# TESTER_SENSOR_HAL_AT24xx.net
KiCad netlist of a schematic drawn in Altium Designer
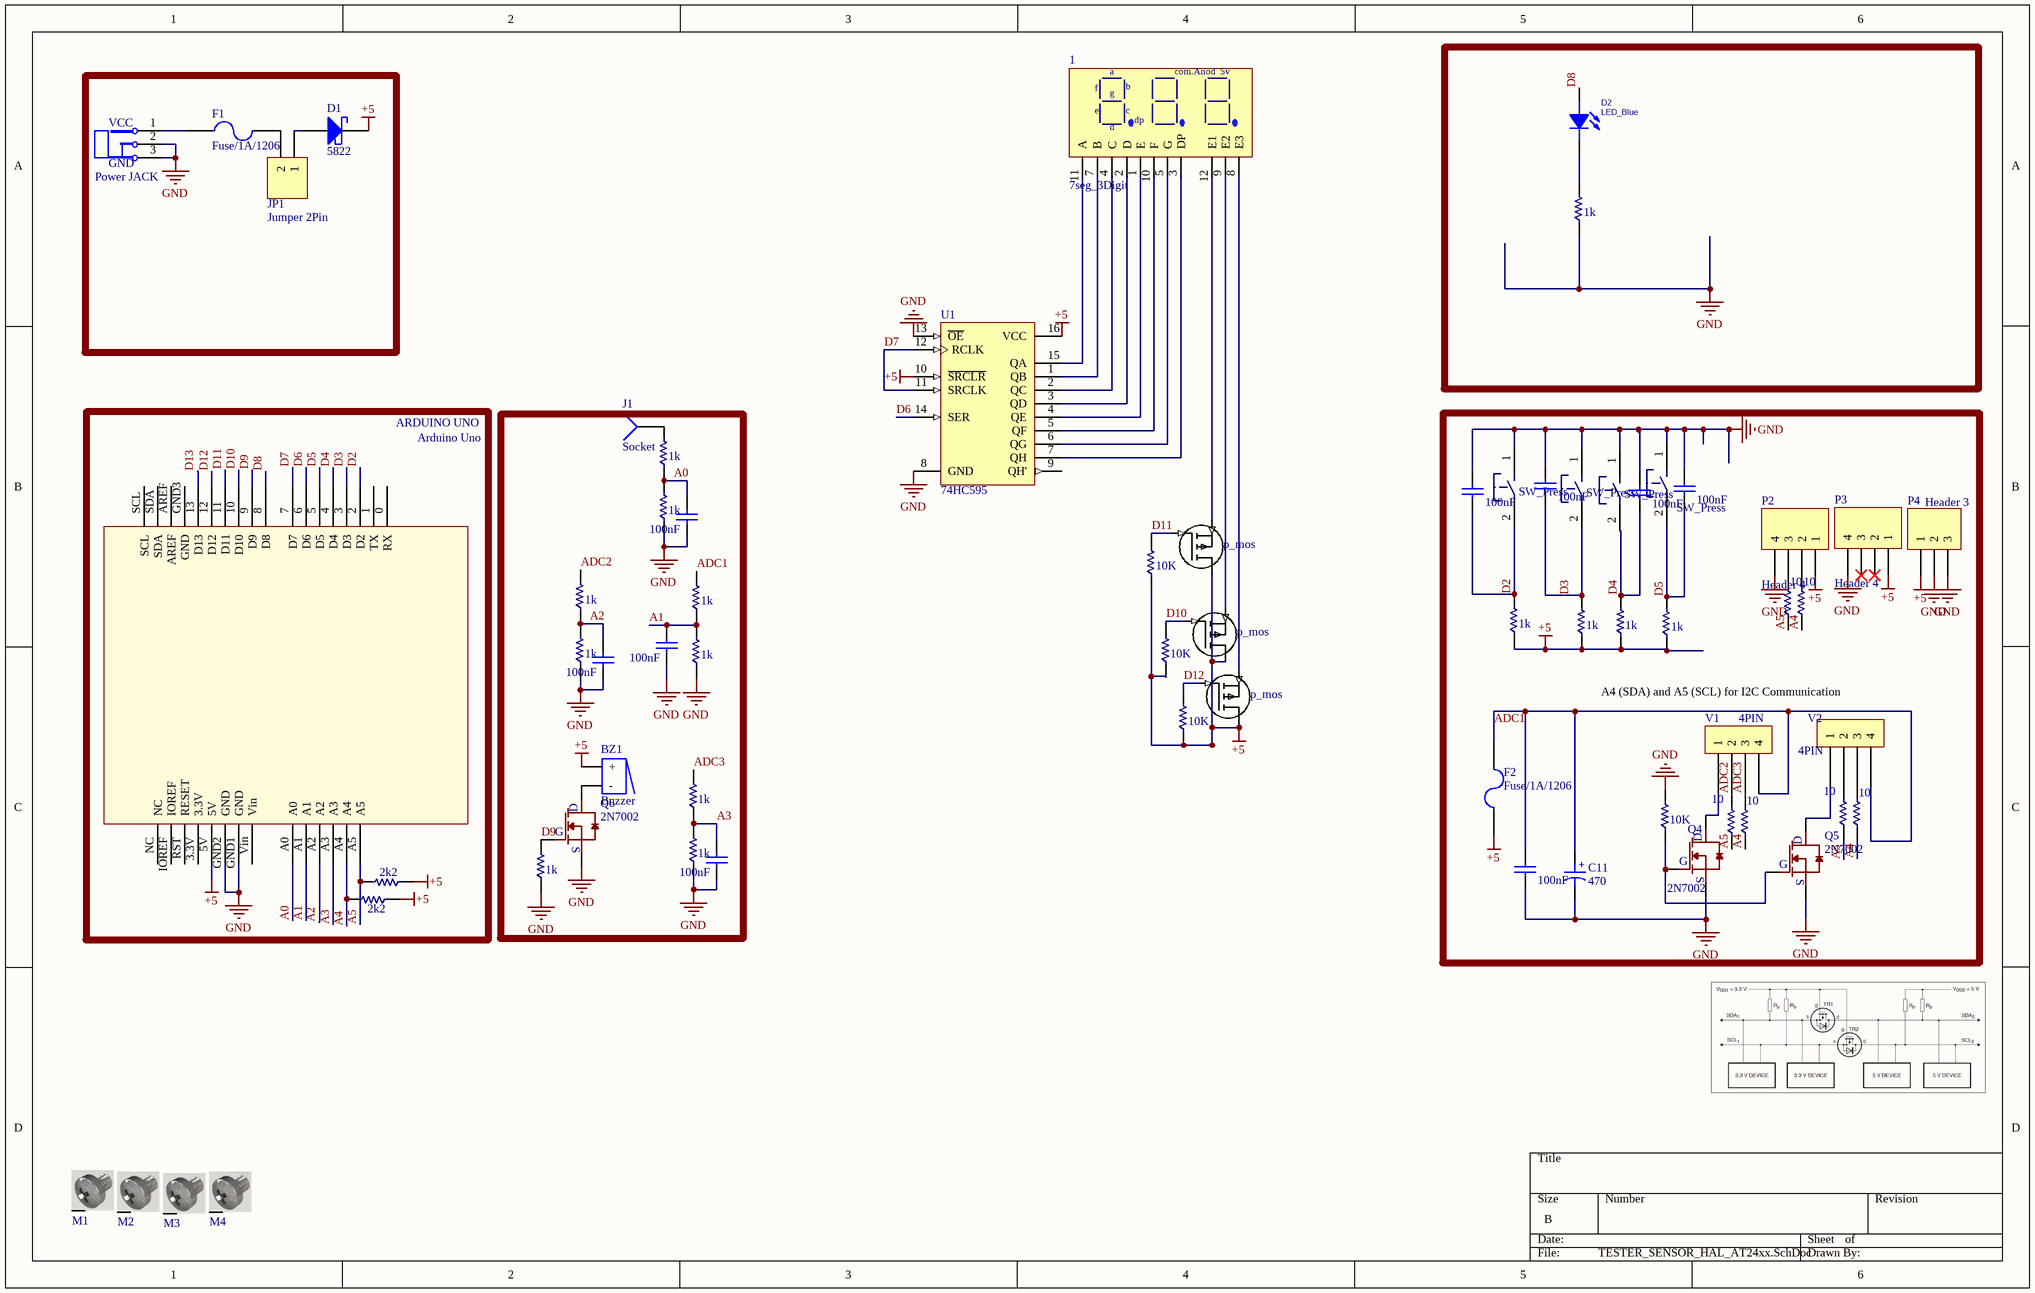
[diagram p0: TESTER_SENSOR_HAL_AT24xx.SchDoc]

(export (version "E")
  (design (tool "Eeschema 10.0.6"))
  (components
    (comp (ref "1")
      (value "7seg_3Digit")
      (footprint "7Segment")
      (description "7Segment-3 Digit- Anode Common")
      (fields (field (name "PART") "7Segment-3Digit"))
      (libsource (lib "R_C_D_T") (part "7Segment-3Digit"))
    )
    (comp (ref "Arduino Uno")
      (value "ARDUINO UNO")
      (footprint "ARDUINO UNO")
      (libsource (lib "Arduino") (part "ARDUINO UNO"))
    )
    (comp (ref "BZ1")
      (value "Buzzer")
      (footprint "Buzzer 3M")
      (fields (field (name "PART") "BUZZER 5V") (field (name "POWER") "CHINA"))
      (libsource (lib "NKH_Contacts") (part "Buzzer_small"))
    )
    (comp (ref "C2")
      (value "100nF")
      (footprint "CAP1206")
      (description "cap_no_polar_seramic_multilayer")
      (fields (field (name "PART") "Cap-smd-1206-100nf"))
      (libsource (lib "R_C_D_T") (part "cap_no_polar_sig"))
    )
    (comp (ref "C3")
      (value "100nF")
      (footprint "CAP1206")
      (description "cap_no_polar_seramic_multilayer")
      (fields (field (name "PART") "Cap-smd-1206-100nf"))
      (libsource (lib "R_C_D_T") (part "cap_no_polar_sig"))
    )
    (comp (ref "C4")
      (value "100nF")
      (footprint "CAP1206")
      (description "cap_no_polar_seramic_multilayer")
      (fields (field (name "PART") "Cap-smd-1206-100nf"))
      (libsource (lib "R_C_D_T") (part "cap_no_polar_sig"))
    )
    (comp (ref "C5")
      (value "100nF")
      (footprint "CAP1206")
      (description "cap_no_polar_seramic_multilayer")
      (fields (field (name "PART") "Cap-smd-1206-100nf"))
      (libsource (lib "R_C_D_T") (part "cap_no_polar_sig"))
    )
    (comp (ref "C6")
      (value "100nF")
      (footprint "CAP1206")
      (description "cap_no_polar_seramic_multilayer")
      (fields (field (name "PART") "Cap-smd-1206-100nf"))
      (libsource (lib "R_C_D_T") (part "cap_no_polar_sig"))
    )
    (comp (ref "C7")
      (value "100nF")
      (footprint "CAP1206")
      (description "cap_no_polar_seramic_multilayer")
      (fields (field (name "PART") "Cap-smd-1206-100nf"))
      (libsource (lib "R_C_D_T") (part "cap_no_polar_sig"))
    )
    (comp (ref "C8")
      (value "100nF")
      (footprint "CAP1206")
      (description "cap_no_polar_seramic_multilayer")
      (fields (field (name "PART") "Cap-smd-1206-100nf"))
      (libsource (lib "R_C_D_T") (part "cap_no_polar_sig"))
    )
    (comp (ref "C9")
      (value "100nF")
      (footprint "CAP1206")
      (description "cap_no_polar_seramic_multilayer")
      (fields (field (name "PART") "Cap-smd-1206-100nf"))
      (libsource (lib "R_C_D_T") (part "cap_no_polar_sig"))
    )
    (comp (ref "C10")
      (value "100nF")
      (footprint "CAP1206")
      (description "cap_no_polar_seramic_multilayer")
      (fields (field (name "PART") "Cap-smd-1206-100nf"))
      (libsource (lib "R_C_D_T") (part "cap_no_polar_sig"))
    )
    (comp (ref "C11")
      (value "470")
      (footprint "CAP_POLAR_8X11.5")
      (description "Cap electrolitic radial")
      (fields (field (name "PART") "Cap-pol-dip-470uf_16V") (field (name "DESIGNER") "rashid_behdarvand"))
      (libsource (lib "R_C_D_T") (part "Cap_polar"))
    )
    (comp (ref "D1")
      (value "5822")
      (footprint "SMA_Diode")
      (fields (field (name "PART") "Diode-shotkey-SMB5822"))
      (libsource (lib "R_C_D_T") (part "Diode_1n5817"))
    )
    (comp (ref "D2")
      (value "LED_Blue")
      (footprint "LED-3mm")
      (description "LED LIGHTING 5mm Blue")
      (fields (field (name "PART") "LED3MM_RED") (field (name "DESIGNER") "Abbas Basereh"))
      (libsource (lib "R_C_D_T") (part "LED5MM_Blue"))
    )
    (comp (ref "F1")
      (value "Fuse")
      (footprint "Fuse 1206 smd")
      (fields (field (name "ALTIUM_UNNAMED_1") "Fuse/1A/1206") (field (name "PART") "Fuse 1206 smd"))
      (libsource (lib "R_C_D_T") (part "Fuse SMT"))
    )
    (comp (ref "F2")
      (value "Fuse")
      (footprint "Fuse 1206 smd")
      (fields (field (name "ALTIUM_UNNAMED_1") "Fuse/1A/1206") (field (name "PART") "Fuse 1206 smd"))
      (libsource (lib "R_C_D_T") (part "Fuse SMT"))
    )
    (comp (ref "J1")
      (value "Socket")
      (footprint "PIN1")
      (fields (field (name "PUBLISHER") "Altium Limited"))
      (libsource (lib "NKH_Contacts") (part "Socket"))
    )
    (comp (ref "JP1")
      (value "Jumper 2Pin")
      (footprint "Jumper Small - 2.54 - RED")
      (description "Jumper, 2-Pin")
      (fields (field (name "DESIGNER") "Abbas Basereh"))
      (libsource (lib "NKH_Contacts") (part "Jumper 2Pin"))
    )
    (comp (ref "M1")
      (value "Screw")
      (footprint "Board Screw_No Silk")
      (description "Board Screw With Spacer")
      (libsource (lib "QUECTEL_MC60") (part "Board Screw"))
    )
    (comp (ref "M2")
      (value "Screw")
      (footprint "Board Screw_No Silk")
      (description "Board Screw With Spacer")
      (libsource (lib "QUECTEL_MC60") (part "Board Screw"))
    )
    (comp (ref "M3")
      (value "Screw")
      (footprint "Board Screw_No Silk")
      (description "Board Screw With Spacer")
      (libsource (lib "QUECTEL_MC60") (part "Board Screw"))
    )
    (comp (ref "M4")
      (value "Screw")
      (footprint "Board Screw_No Silk")
      (description "Board Screw With Spacer")
      (libsource (lib "QUECTEL_MC60") (part "Board Screw"))
    )
    (comp (ref "P1")
      (value "Power JACK")
      (footprint "power jack")
      (fields (field (name "PART") "dc jack adaptor"))
      (libsource (lib "NKH_Contacts") (part "PHONE JACK"))
    )
    (comp (ref "P2")
      (value "Header 4")
      (footprint "HDR1X4")
      (description "Header, 4-Pin")
      (fields (field (name "PUBLISHER") "Altium Limited"))
      (libsource (lib "Miscellaneous Connectors") (part "Header 4"))
    )
    (comp (ref "P3")
      (value "Header 4")
      (footprint "HDR1X4")
      (description "Header, 4-Pin")
      (fields (field (name "PUBLISHER") "Altium Limited"))
      (libsource (lib "Miscellaneous Connectors") (part "Header 4"))
    )
    (comp (ref "P4")
      (value "Header 3")
      (footprint "HDR1X3")
      (description "Header, 3-Pin")
      (fields (field (name "PUBLISHER") "Altium Limited"))
      (libsource (lib "Miscellaneous Connectors") (part "Header 3"))
    )
    (comp (ref "Q1")
      (value "p_mos")
      (footprint "SOT23_BEC_M")
      (description "P CHANNEL MOSFET")
      (fields (field (name "MANUFACTURER") "Diodes Inc") (field (name "PART") "Mosfet-p-channel-AO3401"))
      (libsource (lib "R_C_D_T") (part "p_mos"))
    )
    (comp (ref "Q2")
      (value "p_mos")
      (footprint "SOT23_BEC_M")
      (description "P CHANNEL MOSFET")
      (fields (field (name "MANUFACTURER") "Diodes Inc") (field (name "PART") "Mosfet-p-channel-AO3401"))
      (libsource (lib "R_C_D_T") (part "p_mos"))
    )
    (comp (ref "Q3")
      (value "p_mos")
      (footprint "SOT23_BEC_M")
      (description "P CHANNEL MOSFET")
      (fields (field (name "MANUFACTURER") "Diodes Inc") (field (name "PART") "Mosfet-p-channel-AO3401"))
      (libsource (lib "R_C_D_T") (part "p_mos"))
    )
    (comp (ref "Q4")
      (value "2N7002")
      (footprint "SOT23_BEC_M")
      (fields (field (name "PART") "Mosfet-n-channel-2n7002"))
      (libsource (lib "R_C_D_T") (part "2N7002"))
    )
    (comp (ref "Q5")
      (value "2N7002")
      (footprint "SOT23_BEC_M")
      (fields (field (name "PART") "Mosfet-n-channel-2n7002"))
      (libsource (lib "R_C_D_T") (part "2N7002"))
    )
    (comp (ref "Q6")
      (value "2N7002")
      (footprint "SOT23_BEC_M")
      (fields (field (name "PART") "Mosfet-n-channel-2n7002"))
      (libsource (lib "R_C_D_T") (part "2N7002"))
    )
    (comp (ref "R1")
      (value "1k")
      (footprint "RES1206")
      (fields (field (name "PART") "resistor-smd-1206-1k") (field (name "DESIGNER") "rashid_behdarvand"))
      (libsource (lib "R_C_D_T") (part "resistor"))
    )
    (comp (ref "R2")
      (value "1k")
      (footprint "RES1206")
      (fields (field (name "PART") "resistor-smd-1206-1k") (field (name "DESIGNER") "rashid_behdarvand"))
      (libsource (lib "R_C_D_T") (part "resistor"))
    )
    (comp (ref "R3")
      (value "1k")
      (footprint "RES1206")
      (fields (field (name "PART") "resistor-smd-1206-1k") (field (name "DESIGNER") "rashid_behdarvand"))
      (libsource (lib "R_C_D_T") (part "resistor"))
    )
    (comp (ref "R4")
      (value "1k")
      (footprint "RES1206")
      (fields (field (name "PART") "resistor-smd-1206-1k") (field (name "DESIGNER") "rashid_behdarvand"))
      (libsource (lib "R_C_D_T") (part "resistor"))
    )
    (comp (ref "R5")
      (value "10")
      (footprint "RES1206")
      (fields (field (name "PART") "resistor-smd-1206-1k") (field (name "DESIGNER") "rashid_behdarvand"))
      (libsource (lib "R_C_D_T") (part "resistor"))
    )
    (comp (ref "R6")
      (value "10")
      (footprint "RES1206")
      (fields (field (name "PART") "resistor-smd-1206-1k") (field (name "DESIGNER") "rashid_behdarvand"))
      (libsource (lib "R_C_D_T") (part "resistor"))
    )
    (comp (ref "R7")
      (value "1k")
      (footprint "RES1206")
      (fields (field (name "PART") "resistor-smd-1206-1k") (field (name "DESIGNER") "rashid_behdarvand"))
      (libsource (lib "R_C_D_T") (part "resistor"))
    )
    (comp (ref "R8")
      (value "1k")
      (footprint "RES1206")
      (fields (field (name "PART") "resistor-smd-1206-1k") (field (name "DESIGNER") "rashid_behdarvand"))
      (libsource (lib "R_C_D_T") (part "resistor"))
    )
    (comp (ref "R9")
      (value "1k")
      (footprint "RES1206")
      (fields (field (name "PART") "resistor-smd-1206-1k") (field (name "DESIGNER") "rashid_behdarvand"))
      (libsource (lib "R_C_D_T") (part "resistor"))
    )
    (comp (ref "R10")
      (value "10")
      (footprint "RES1206")
      (fields (field (name "PART") "resistor-smd-1206-1k") (field (name "DESIGNER") "rashid_behdarvand"))
      (libsource (lib "R_C_D_T") (part "resistor"))
    )
    (comp (ref "R11")
      (value "10")
      (footprint "RES1206")
      (fields (field (name "PART") "resistor-smd-1206-1k") (field (name "DESIGNER") "rashid_behdarvand"))
      (libsource (lib "R_C_D_T") (part "resistor"))
    )
    (comp (ref "R12")
      (value "10")
      (footprint "RES1206")
      (fields (field (name "PART") "resistor-smd-1206-1k") (field (name "DESIGNER") "rashid_behdarvand"))
      (libsource (lib "R_C_D_T") (part "resistor"))
    )
    (comp (ref "R13")
      (value "10")
      (footprint "RES1206")
      (fields (field (name "PART") "resistor-smd-1206-1k") (field (name "DESIGNER") "rashid_behdarvand"))
      (libsource (lib "R_C_D_T") (part "resistor"))
    )
    (comp (ref "R14")
      (value "1k")
      (footprint "RES1206")
      (fields (field (name "PART") "resistor-smd-1206-1k") (field (name "DESIGNER") "rashid_behdarvand"))
      (libsource (lib "R_C_D_T") (part "resistor"))
    )
    (comp (ref "R15")
      (value "1k")
      (footprint "RES1206")
      (fields (field (name "PART") "resistor-smd-1206-1k") (field (name "DESIGNER") "rashid_behdarvand"))
      (libsource (lib "R_C_D_T") (part "resistor"))
    )
    (comp (ref "R16")
      (value "2k2")
      (footprint "RES1206")
      (fields (field (name "PART") "resistor-smd-1206-1k") (field (name "DESIGNER") "rashid_behdarvand"))
      (libsource (lib "R_C_D_T") (part "resistor"))
    )
    (comp (ref "R17")
      (value "2k2")
      (footprint "RES1206")
      (fields (field (name "PART") "resistor-smd-1206-1k") (field (name "DESIGNER") "rashid_behdarvand"))
      (libsource (lib "R_C_D_T") (part "resistor"))
    )
    (comp (ref "R18")
      (value "10K")
      (footprint "RES1206")
      (fields (field (name "PART") "resistor-smd-1206-1k") (field (name "DESIGNER") "rashid_behdarvand"))
      (libsource (lib "R_C_D_T") (part "resistor"))
    )
    (comp (ref "R19")
      (value "10K")
      (footprint "RES1206")
      (fields (field (name "PART") "resistor-smd-1206-1k") (field (name "DESIGNER") "rashid_behdarvand"))
      (libsource (lib "R_C_D_T") (part "resistor"))
    )
    (comp (ref "R20")
      (value "10K")
      (footprint "RES1206")
      (fields (field (name "PART") "resistor-smd-1206-1k") (field (name "DESIGNER") "rashid_behdarvand"))
      (libsource (lib "R_C_D_T") (part "resistor"))
    )
    (comp (ref "R21")
      (value "10K")
      (footprint "RES1206")
      (fields (field (name "PART") "resistor-smd-1206-1k") (field (name "DESIGNER") "rashid_behdarvand"))
      (libsource (lib "R_C_D_T") (part "resistor"))
    )
    (comp (ref "res1")
      (value "1k")
      (footprint "RES1206")
      (fields (field (name "PART") "resistor-smd-1206-1k") (field (name "DESIGNER") "rashid_behdarvand"))
      (libsource (lib "R_C_D_T") (part "resistor"))
    )
    (comp (ref "res5")
      (value "1k")
      (footprint "RES1206")
      (fields (field (name "PART") "resistor-smd-1206-1k") (field (name "DESIGNER") "rashid_behdarvand"))
      (libsource (lib "R_C_D_T") (part "resistor"))
    )
    (comp (ref "res6")
      (value "1k")
      (footprint "RES1206")
      (fields (field (name "PART") "resistor-smd-1206-1k") (field (name "DESIGNER") "rashid_behdarvand"))
      (libsource (lib "R_C_D_T") (part "resistor"))
    )
    (comp (ref "res7")
      (value "1k")
      (footprint "RES1206")
      (fields (field (name "PART") "resistor-smd-1206-1k") (field (name "DESIGNER") "rashid_behdarvand"))
      (libsource (lib "R_C_D_T") (part "resistor"))
    )
    (comp (ref "res8")
      (value "1k")
      (footprint "RES1206")
      (fields (field (name "PART") "resistor-smd-1206-1k") (field (name "DESIGNER") "rashid_behdarvand"))
      (libsource (lib "R_C_D_T") (part "resistor"))
    )
    (comp (ref "sw1")
      (value "SW_Press")
      (footprint "tact_kfc-12x12")
      (description "small tac switch")
      (fields (field (name "PART") "tac switch kfc-12x12x12"))
      (libsource (lib "NKH_Contacts") (part "Tac switch"))
    )
    (comp (ref "sw3")
      (value "SW_Press")
      (footprint "tact_kfc-12x12")
      (description "small tac switch")
      (fields (field (name "PART") "tac switch kfc-12x12x12"))
      (libsource (lib "NKH_Contacts") (part "Tac switch"))
    )
    (comp (ref "sw4")
      (value "SW_Press")
      (footprint "tact_kfc-12x12")
      (description "small tac switch")
      (fields (field (name "PART") "tac switch kfc-12x12x12"))
      (libsource (lib "NKH_Contacts") (part "Tac switch"))
    )
    (comp (ref "sw5")
      (value "SW_Press")
      (footprint "tact_kfc-12x12")
      (description "small tac switch")
      (fields (field (name "PART") "tac switch kfc-12x12x12"))
      (libsource (lib "NKH_Contacts") (part "Tac switch"))
    )
    (comp (ref "U1")
      (value "74HC595")
      (footprint "SO16_N")
      (description "8 Bit Shift Register with Output Latches (3 STATE)")
      (fields (field (name "PART") "74HC595 SMD") (field (name "PUBLISHER") "Altium Limited"))
      (libsource (lib "NKH_IC") (part "M74HC595M1R"))
    )
    (comp (ref "V1")
      (value "4PIN")
      (footprint "4PIN")
      (description "connector power 4pin stright lock")
      (fields (field (name "PART") "VH_ST_4pin"))
      (libsource (lib "NKH_Contacts") (part "VH_ST_4pin"))
    )
    (comp (ref "V2")
      (value "4PIN")
      (footprint "4PIN")
      (description "connector power 4pin stright lock")
      (fields (field (name "PART") "VH_ST_4pin"))
      (libsource (lib "NKH_Contacts") (part "VH_ST_4pin"))
    )
  )
  (nets
    (net (code "1") (name "+5") (class "Default")
      (node (ref "Arduino Uno") (pin "5V") (pinfunction "5V_5V") (pintype "passive"))
      (node (ref "BZ1") (pin "1") (pinfunction "+_1") (pintype "passive"))
      (node (ref "D1") (pin "2") (pinfunction "K_2") (pintype "passive"))
      (node (ref "F2") (pin "2") (pinfunction "2_2") (pintype "passive"))
      (node (ref "P2") (pin "1") (pinfunction "1_1") (pintype "passive"))
      (node (ref "P3") (pin "1") (pinfunction "1_1") (pintype "passive"))
      (node (ref "P4") (pin "1") (pinfunction "1_1") (pintype "passive"))
      (node (ref "Q1") (pin "3") (pintype "passive"))
      (node (ref "Q2") (pin "3") (pintype "passive"))
      (node (ref "Q3") (pin "3") (pintype "passive"))
      (node (ref "R16") (pin "1") (pinfunction "1_1") (pintype "passive"))
      (node (ref "R17") (pin "1") (pinfunction "1_1") (pintype "passive"))
      (node (ref "R18") (pin "1") (pinfunction "1_1") (pintype "passive"))
      (node (ref "R19") (pin "1") (pinfunction "1_1") (pintype "passive"))
      (node (ref "R20") (pin "1") (pinfunction "1_1") (pintype "passive"))
      (node (ref "U1") (pin "10") (pinfunction "~{SRCLR}_10") (pintype "input"))
      (node (ref "U1") (pin "16") (pinfunction "VCC_16") (pintype "power_in"))
      (node (ref "res5") (pin "1") (pinfunction "1_1") (pintype "passive"))
      (node (ref "res6") (pin "1") (pinfunction "1_1") (pintype "passive"))
      (node (ref "res7") (pin "1") (pinfunction "1_1") (pintype "passive"))
      (node (ref "res8") (pin "1") (pinfunction "1_1") (pintype "passive"))
    )
    (net (code "2") (name "/A0") (class "Default")
      (node (ref "Arduino Uno") (pin "A0") (pinfunction "A0_A0") (pintype "passive"))
      (node (ref "C6") (pin "2") (pinfunction "2_2") (pintype "passive"))
      (node (ref "R1") (pin "1") (pinfunction "1_1") (pintype "passive"))
      (node (ref "R2") (pin "2") (pinfunction "2_2") (pintype "passive"))
    )
    (net (code "3") (name "/A1") (class "Default")
      (node (ref "Arduino Uno") (pin "A1") (pinfunction "A1_A1") (pintype "passive"))
      (node (ref "C7") (pin "2") (pinfunction "2_2") (pintype "passive"))
      (node (ref "R4") (pin "1") (pinfunction "1_1") (pintype "passive"))
      (node (ref "R8") (pin "2") (pinfunction "2_2") (pintype "passive"))
    )
    (net (code "4") (name "/A2") (class "Default")
      (node (ref "Arduino Uno") (pin "A2") (pinfunction "A2_A2") (pintype "passive"))
      (node (ref "C8") (pin "2") (pinfunction "2_2") (pintype "passive"))
      (node (ref "R3") (pin "1") (pinfunction "1_1") (pintype "passive"))
      (node (ref "R7") (pin "2") (pinfunction "2_2") (pintype "passive"))
    )
    (net (code "5") (name "/A3") (class "Default")
      (node (ref "Arduino Uno") (pin "A3") (pinfunction "A3_A3") (pintype "passive"))
      (node (ref "C9") (pin "2") (pinfunction "2_2") (pintype "passive"))
      (node (ref "R14") (pin "2") (pinfunction "2_2") (pintype "passive"))
      (node (ref "R9") (pin "1") (pinfunction "1_1") (pintype "passive"))
    )
    (net (code "6") (name "/A4") (class "Default")
      (node (ref "Arduino Uno") (pin "A4") (pinfunction "A4_A4") (pintype "passive"))
      (node (ref "R11") (pin "1") (pinfunction "1_1") (pintype "passive"))
      (node (ref "R13") (pin "1") (pinfunction "1_1") (pintype "passive"))
      (node (ref "R17") (pin "2") (pinfunction "2_2") (pintype "passive"))
      (node (ref "R6") (pin "1") (pinfunction "1_1") (pintype "passive"))
    )
    (net (code "7") (name "/A5") (class "Default")
      (node (ref "Arduino Uno") (pin "A5") (pinfunction "A5_A5") (pintype "passive"))
      (node (ref "R10") (pin "1") (pinfunction "1_1") (pintype "passive"))
      (node (ref "R12") (pin "1") (pinfunction "1_1") (pintype "passive"))
      (node (ref "R16") (pin "2") (pinfunction "2_2") (pintype "passive"))
      (node (ref "R5") (pin "1") (pinfunction "1_1") (pintype "passive"))
    )
    (net (code "8") (name "/ADC1") (class "Default")
      (node (ref "C10") (pin "2") (pinfunction "2_2") (pintype "passive"))
      (node (ref "C11") (pin "1") (pinfunction "1_1") (pintype "passive"))
      (node (ref "F2") (pin "1") (pinfunction "1_1") (pintype "passive"))
      (node (ref "R4") (pin "2") (pinfunction "2_2") (pintype "passive"))
      (node (ref "V1") (pin "4") (pinfunction "4_4") (pintype "passive"))
      (node (ref "V2") (pin "4") (pinfunction "4_4") (pintype "passive"))
    )
    (net (code "9") (name "/ADC2") (class "Default")
      (node (ref "R12") (pin "2") (pinfunction "2_2") (pintype "passive"))
      (node (ref "R3") (pin "2") (pinfunction "2_2") (pintype "passive"))
      (node (ref "V1") (pin "2") (pinfunction "2_2") (pintype "passive"))
    )
    (net (code "10") (name "/ADC3") (class "Default")
      (node (ref "R13") (pin "2") (pinfunction "2_2") (pintype "passive"))
      (node (ref "R9") (pin "2") (pinfunction "2_2") (pintype "passive"))
      (node (ref "V1") (pin "3") (pinfunction "3_3") (pintype "passive"))
    )
    (net (code "11") (name "/D2") (class "Default")
      (node (ref "Arduino Uno") (pin "2") (pinfunction "D2_2") (pintype "passive"))
      (node (ref "C4") (pin "1") (pinfunction "1_1") (pintype "passive"))
      (node (ref "res5") (pin "2") (pinfunction "2_2") (pintype "passive"))
      (node (ref "sw3") (pin "2") (pinfunction "2_2") (pintype "passive"))
    )
    (net (code "12") (name "/D3") (class "Default")
      (node (ref "Arduino Uno") (pin "3") (pinfunction "D3_3") (pintype "passive"))
      (node (ref "C2") (pin "1") (pinfunction "1_1") (pintype "passive"))
      (node (ref "res6") (pin "2") (pinfunction "2_2") (pintype "passive"))
      (node (ref "sw5") (pin "2") (pinfunction "2_2") (pintype "passive"))
    )
    (net (code "13") (name "/D4") (class "Default")
      (node (ref "Arduino Uno") (pin "4") (pinfunction "D4_4") (pintype "passive"))
      (node (ref "C5") (pin "1") (pinfunction "1_1") (pintype "passive"))
      (node (ref "res7") (pin "2") (pinfunction "2_2") (pintype "passive"))
      (node (ref "sw4") (pin "2") (pinfunction "2_2") (pintype "passive"))
    )
    (net (code "14") (name "/D5") (class "Default")
      (node (ref "Arduino Uno") (pin "5") (pinfunction "D5_5") (pintype "passive"))
      (node (ref "C3") (pin "1") (pinfunction "1_1") (pintype "passive"))
      (node (ref "res8") (pin "2") (pinfunction "2_2") (pintype "passive"))
      (node (ref "sw1") (pin "2") (pinfunction "2_2") (pintype "passive"))
    )
    (net (code "15") (name "/D6") (class "Default")
      (node (ref "Arduino Uno") (pin "6") (pinfunction "D6_6") (pintype "passive"))
      (node (ref "U1") (pin "14") (pinfunction "SER_14") (pintype "input"))
    )
    (net (code "16") (name "/D7") (class "Default")
      (node (ref "Arduino Uno") (pin "7") (pinfunction "D7_7") (pintype "passive"))
      (node (ref "U1") (pin "11") (pinfunction "SRCLK_11") (pintype "input"))
      (node (ref "U1") (pin "12") (pinfunction "RCLK_12") (pintype "input"))
    )
    (net (code "17") (name "/D8") (class "Default")
      (node (ref "Arduino Uno") (pin "8") (pinfunction "D8_8") (pintype "passive"))
      (node (ref "D2") (pin "1") (pinfunction "ANODE_1") (pintype "passive"))
    )
    (net (code "18") (name "/D9") (class "Default")
      (node (ref "Arduino Uno") (pin "9") (pinfunction "D9_9") (pintype "passive"))
      (node (ref "Q6") (pin "1") (pinfunction "G_1") (pintype "passive"))
      (node (ref "R15") (pin "2") (pinfunction "2_2") (pintype "passive"))
    )
    (net (code "19") (name "/D10") (class "Default")
      (node (ref "Arduino Uno") (pin "10") (pinfunction "D10_10") (pintype "passive"))
      (node (ref "Q2") (pin "1") (pintype "input"))
      (node (ref "R19") (pin "2") (pinfunction "2_2") (pintype "passive"))
    )
    (net (code "20") (name "/D11") (class "Default")
      (node (ref "Arduino Uno") (pin "11") (pinfunction "D11_11") (pintype "passive"))
      (node (ref "Q1") (pin "1") (pintype "input"))
      (node (ref "R18") (pin "2") (pinfunction "2_2") (pintype "passive"))
    )
    (net (code "21") (name "/D12") (class "Default")
      (node (ref "Arduino Uno") (pin "12") (pinfunction "D12_12") (pintype "passive"))
      (node (ref "Q3") (pin "1") (pintype "input"))
      (node (ref "R20") (pin "2") (pinfunction "2_2") (pintype "passive"))
    )
    (net (code "22") (name "/D13") (class "Default")
      (node (ref "Arduino Uno") (pin "13") (pinfunction "D13_13") (pintype "passive"))
    )
    (net (code "23") (name "GND") (class "Default")
      (node (ref "Arduino Uno") (pin "GND1") (pinfunction "GND_GND1") (pintype "passive"))
      (node (ref "Arduino Uno") (pin "GND2") (pinfunction "GND_GND2") (pintype "passive"))
      (node (ref "C10") (pin "1") (pinfunction "1_1") (pintype "passive"))
      (node (ref "C11") (pin "2") (pinfunction "2_2") (pintype "passive"))
      (node (ref "C2") (pin "2") (pinfunction "2_2") (pintype "passive"))
      (node (ref "C3") (pin "2") (pinfunction "2_2") (pintype "passive"))
      (node (ref "C4") (pin "2") (pinfunction "2_2") (pintype "passive"))
      (node (ref "C5") (pin "2") (pinfunction "2_2") (pintype "passive"))
      (node (ref "C6") (pin "1") (pinfunction "1_1") (pintype "passive"))
      (node (ref "C7") (pin "1") (pinfunction "1_1") (pintype "passive"))
      (node (ref "C8") (pin "1") (pinfunction "1_1") (pintype "passive"))
      (node (ref "C9") (pin "1") (pinfunction "1_1") (pintype "passive"))
      (node (ref "P1") (pin "2") (pinfunction "2_2") (pintype "passive"))
      (node (ref "P1") (pin "3") (pinfunction "3_3") (pintype "passive"))
      (node (ref "P2") (pin "4") (pinfunction "4_4") (pintype "passive"))
      (node (ref "P3") (pin "4") (pinfunction "4_4") (pintype "passive"))
      (node (ref "P4") (pin "2") (pinfunction "2_2") (pintype "passive"))
      (node (ref "P4") (pin "3") (pinfunction "3_3") (pintype "passive"))
      (node (ref "Q4") (pin "2") (pinfunction "S_2") (pintype "passive"))
      (node (ref "Q5") (pin "2") (pinfunction "S_2") (pintype "passive"))
      (node (ref "Q6") (pin "2") (pinfunction "S_2") (pintype "passive"))
      (node (ref "R14") (pin "1") (pinfunction "1_1") (pintype "passive"))
      (node (ref "R15") (pin "1") (pinfunction "1_1") (pintype "passive"))
      (node (ref "R2") (pin "1") (pinfunction "1_1") (pintype "passive"))
      (node (ref "R21") (pin "2") (pinfunction "2_2") (pintype "passive"))
      (node (ref "R7") (pin "1") (pinfunction "1_1") (pintype "passive"))
      (node (ref "R8") (pin "1") (pinfunction "1_1") (pintype "passive"))
      (node (ref "U1") (pin "13") (pinfunction "~{OE}_13") (pintype "input"))
      (node (ref "U1") (pin "8") (pinfunction "GND_8") (pintype "power_in"))
      (node (ref "res1") (pin "1") (pinfunction "1_1") (pintype "passive"))
      (node (ref "sw1") (pin "1") (pinfunction "1_1") (pintype "passive"))
      (node (ref "sw3") (pin "1") (pinfunction "1_1") (pintype "passive"))
      (node (ref "sw4") (pin "1") (pinfunction "1_1") (pintype "passive"))
      (node (ref "sw5") (pin "1") (pinfunction "1_1") (pintype "passive"))
    )
    (net (code "24") (name "Net-(1-A)") (class "Default")
      (node (ref "1") (pin "11") (pinfunction "A_11") (pintype "passive"))
      (node (ref "U1") (pin "15") (pinfunction "QA_15") (pintype "tri_state"))
    )
    (net (code "25") (name "Net-(1-B)") (class "Default")
      (node (ref "1") (pin "7") (pinfunction "B_7") (pintype "passive"))
      (node (ref "U1") (pin "1") (pinfunction "QB_1") (pintype "tri_state"))
    )
    (net (code "26") (name "Net-(1-C)") (class "Default")
      (node (ref "1") (pin "4") (pinfunction "C_4") (pintype "passive"))
      (node (ref "U1") (pin "2") (pinfunction "QC_2") (pintype "tri_state"))
    )
    (net (code "27") (name "Net-(1-D)") (class "Default")
      (node (ref "1") (pin "2") (pinfunction "D_2") (pintype "passive"))
      (node (ref "U1") (pin "3") (pinfunction "QD_3") (pintype "tri_state"))
    )
    (net (code "28") (name "Net-(1-DP)") (class "Default")
      (node (ref "1") (pin "3") (pinfunction "DP_3") (pintype "passive"))
      (node (ref "U1") (pin "7") (pinfunction "QH_7") (pintype "tri_state"))
    )
    (net (code "29") (name "Net-(1-E)") (class "Default")
      (node (ref "1") (pin "1") (pinfunction "E_1") (pintype "passive"))
      (node (ref "U1") (pin "4") (pinfunction "QE_4") (pintype "tri_state"))
    )
    (net (code "30") (name "Net-(1-E1)") (class "Default")
      (node (ref "1") (pin "12") (pinfunction "E1_12") (pintype "passive"))
      (node (ref "Q1") (pin "2") (pintype "input"))
    )
    (net (code "31") (name "Net-(1-E2)") (class "Default")
      (node (ref "1") (pin "9") (pinfunction "E2_9") (pintype "passive"))
      (node (ref "Q2") (pin "2") (pintype "input"))
    )
    (net (code "32") (name "Net-(1-E3)") (class "Default")
      (node (ref "1") (pin "8") (pinfunction "E3_8") (pintype "passive"))
      (node (ref "Q3") (pin "2") (pintype "input"))
    )
    (net (code "33") (name "Net-(1-F)") (class "Default")
      (node (ref "1") (pin "10") (pinfunction "F_10") (pintype "passive"))
      (node (ref "U1") (pin "5") (pinfunction "QF_5") (pintype "tri_state"))
    )
    (net (code "34") (name "Net-(1-G)") (class "Default")
      (node (ref "1") (pin "5") (pinfunction "G_5") (pintype "passive"))
      (node (ref "U1") (pin "6") (pinfunction "QG_6") (pintype "tri_state"))
    )
    (net (code "35") (name "Net-(BZ1--)") (class "Default")
      (node (ref "BZ1") (pin "2") (pinfunction "-_2") (pintype "passive"))
      (node (ref "Q6") (pin "3") (pinfunction "D_3") (pintype "passive"))
    )
    (net (code "36") (name "Net-(D1-A)") (class "Default")
      (node (ref "D1") (pin "1") (pinfunction "A_1") (pintype "passive"))
      (node (ref "JP1") (pin "1") (pinfunction "1_1") (pintype "passive"))
    )
    (net (code "37") (name "Net-(D2-CATHODE)") (class "Default")
      (node (ref "D2") (pin "2") (pinfunction "CATHODE_2") (pintype "passive"))
      (node (ref "res1") (pin "2") (pinfunction "2_2") (pintype "passive"))
    )
    (net (code "38") (name "Net-(F1-Pad1)") (class "Default")
      (node (ref "F1") (pin "1") (pinfunction "1_1") (pintype "passive"))
      (node (ref "P1") (pin "1") (pinfunction "1_1") (pintype "passive"))
    )
    (net (code "39") (name "Net-(F1-Pad2)") (class "Default")
      (node (ref "F1") (pin "2") (pinfunction "2_2") (pintype "passive"))
      (node (ref "JP1") (pin "2") (pinfunction "2_2") (pintype "passive"))
    )
    (net (code "40") (name "Net-(J1-Pad1)") (class "Default")
      (node (ref "J1") (pin "1") (pinfunction "1_1") (pintype "passive"))
      (node (ref "R1") (pin "2") (pinfunction "2_2") (pintype "passive"))
    )
    (net (code "41") (name "Net-(P2-Pad2)") (class "Default")
      (node (ref "P2") (pin "2") (pinfunction "2_2") (pintype "passive"))
      (node (ref "R6") (pin "2") (pinfunction "2_2") (pintype "passive"))
    )
    (net (code "42") (name "Net-(P2-Pad3)") (class "Default")
      (node (ref "P2") (pin "3") (pinfunction "3_3") (pintype "passive"))
      (node (ref "R5") (pin "2") (pinfunction "2_2") (pintype "passive"))
    )
    (net (code "43") (name "Net-(Q4-D)") (class "Default")
      (node (ref "Q4") (pin "3") (pinfunction "D_3") (pintype "passive"))
      (node (ref "V1") (pin "1") (pinfunction "1_1") (pintype "passive"))
    )
    (net (code "44") (name "Net-(Q4-G)") (class "Default")
      (node (ref "Q4") (pin "1") (pinfunction "G_1") (pintype "passive"))
      (node (ref "Q5") (pin "1") (pinfunction "G_1") (pintype "passive"))
      (node (ref "R21") (pin "1") (pinfunction "1_1") (pintype "passive"))
    )
    (net (code "45") (name "Net-(Q5-D)") (class "Default")
      (node (ref "Q5") (pin "3") (pinfunction "D_3") (pintype "passive"))
      (node (ref "V2") (pin "1") (pinfunction "1_1") (pintype "passive"))
    )
    (net (code "46") (name "Net-(R10-Pad2)") (class "Default")
      (node (ref "R10") (pin "2") (pinfunction "2_2") (pintype "passive"))
      (node (ref "V2") (pin "2") (pinfunction "2_2") (pintype "passive"))
    )
    (net (code "47") (name "Net-(R11-Pad2)") (class "Default")
      (node (ref "R11") (pin "2") (pinfunction "2_2") (pintype "passive"))
      (node (ref "V2") (pin "3") (pinfunction "3_3") (pintype "passive"))
    )
    (net (code "48") (name "unconnected-(Arduino Uno-GND-PadGND3)") (class "Default")
      (node (ref "Arduino Uno") (pin "GND3") (pinfunction "GND_GND3") (pintype "passive"))
    )
    (net (code "49") (name "unconnected-(Arduino Uno-Pad3.3V)") (class "Default")
      (node (ref "Arduino Uno") (pin "3.3V") (pinfunction "3.3V_3.3V") (pintype "passive"))
    )
    (net (code "50") (name "unconnected-(Arduino Uno-PadAREF)") (class "Default")
      (node (ref "Arduino Uno") (pin "AREF") (pinfunction "AREF_AREF") (pintype "passive"))
    )
    (net (code "51") (name "unconnected-(Arduino Uno-PadIOREF)") (class "Default")
      (node (ref "Arduino Uno") (pin "IOREF") (pinfunction "IOREF_IOREF") (pintype "passive"))
    )
    (net (code "52") (name "unconnected-(Arduino Uno-PadNC)") (class "Default")
      (node (ref "Arduino Uno") (pin "NC") (pinfunction "NC_NC") (pintype "passive"))
    )
    (net (code "53") (name "unconnected-(Arduino Uno-PadSCL)") (class "Default")
      (node (ref "Arduino Uno") (pin "SCL") (pinfunction "SCL_SCL") (pintype "passive"))
    )
    (net (code "54") (name "unconnected-(Arduino Uno-PadSDA)") (class "Default")
      (node (ref "Arduino Uno") (pin "SDA") (pinfunction "SDA_SDA") (pintype "passive"))
    )
    (net (code "55") (name "unconnected-(Arduino Uno-PadVin)") (class "Default")
      (node (ref "Arduino Uno") (pin "Vin") (pinfunction "Vin_Vin") (pintype "passive"))
    )
    (net (code "56") (name "unconnected-(Arduino Uno-RESET-PadRST)") (class "Default")
      (node (ref "Arduino Uno") (pin "RST") (pinfunction "RESET_RST") (pintype "passive"))
    )
    (net (code "57") (name "unconnected-(Arduino Uno-RX-Pad0)") (class "Default")
      (node (ref "Arduino Uno") (pin "0") (pinfunction "RX_0") (pintype "passive"))
    )
    (net (code "58") (name "unconnected-(Arduino Uno-TX-Pad1)") (class "Default")
      (node (ref "Arduino Uno") (pin "1") (pinfunction "TX_1") (pintype "passive"))
    )
    (net (code "59") (name "unconnected-(M1-PadS)") (class "Default")
      (node (ref "M1") (pin "S") (pinfunction "S_S") (pintype "passive"))
    )
    (net (code "60") (name "unconnected-(M2-PadS)") (class "Default")
      (node (ref "M2") (pin "S") (pinfunction "S_S") (pintype "passive"))
    )
    (net (code "61") (name "unconnected-(M3-PadS)") (class "Default")
      (node (ref "M3") (pin "S") (pinfunction "S_S") (pintype "passive"))
    )
    (net (code "62") (name "unconnected-(M4-PadS)") (class "Default")
      (node (ref "M4") (pin "S") (pinfunction "S_S") (pintype "passive"))
    )
    (net (code "63") (name "unconnected-(P3-Pad2)") (class "Default")
      (node (ref "P3") (pin "2") (pinfunction "2_2") (pintype "passive+no_connect"))
    )
    (net (code "64") (name "unconnected-(P3-Pad3)") (class "Default")
      (node (ref "P3") (pin "3") (pinfunction "3_3") (pintype "passive+no_connect"))
    )
    (net (code "65") (name "unconnected-(U1-QH'-Pad9)") (class "Default")
      (node (ref "U1") (pin "9") (pinfunction "QH'_9") (pintype "output"))
    )
  )
)
